# Main.net
KiCad netlist of a schematic drawn in EAGLE
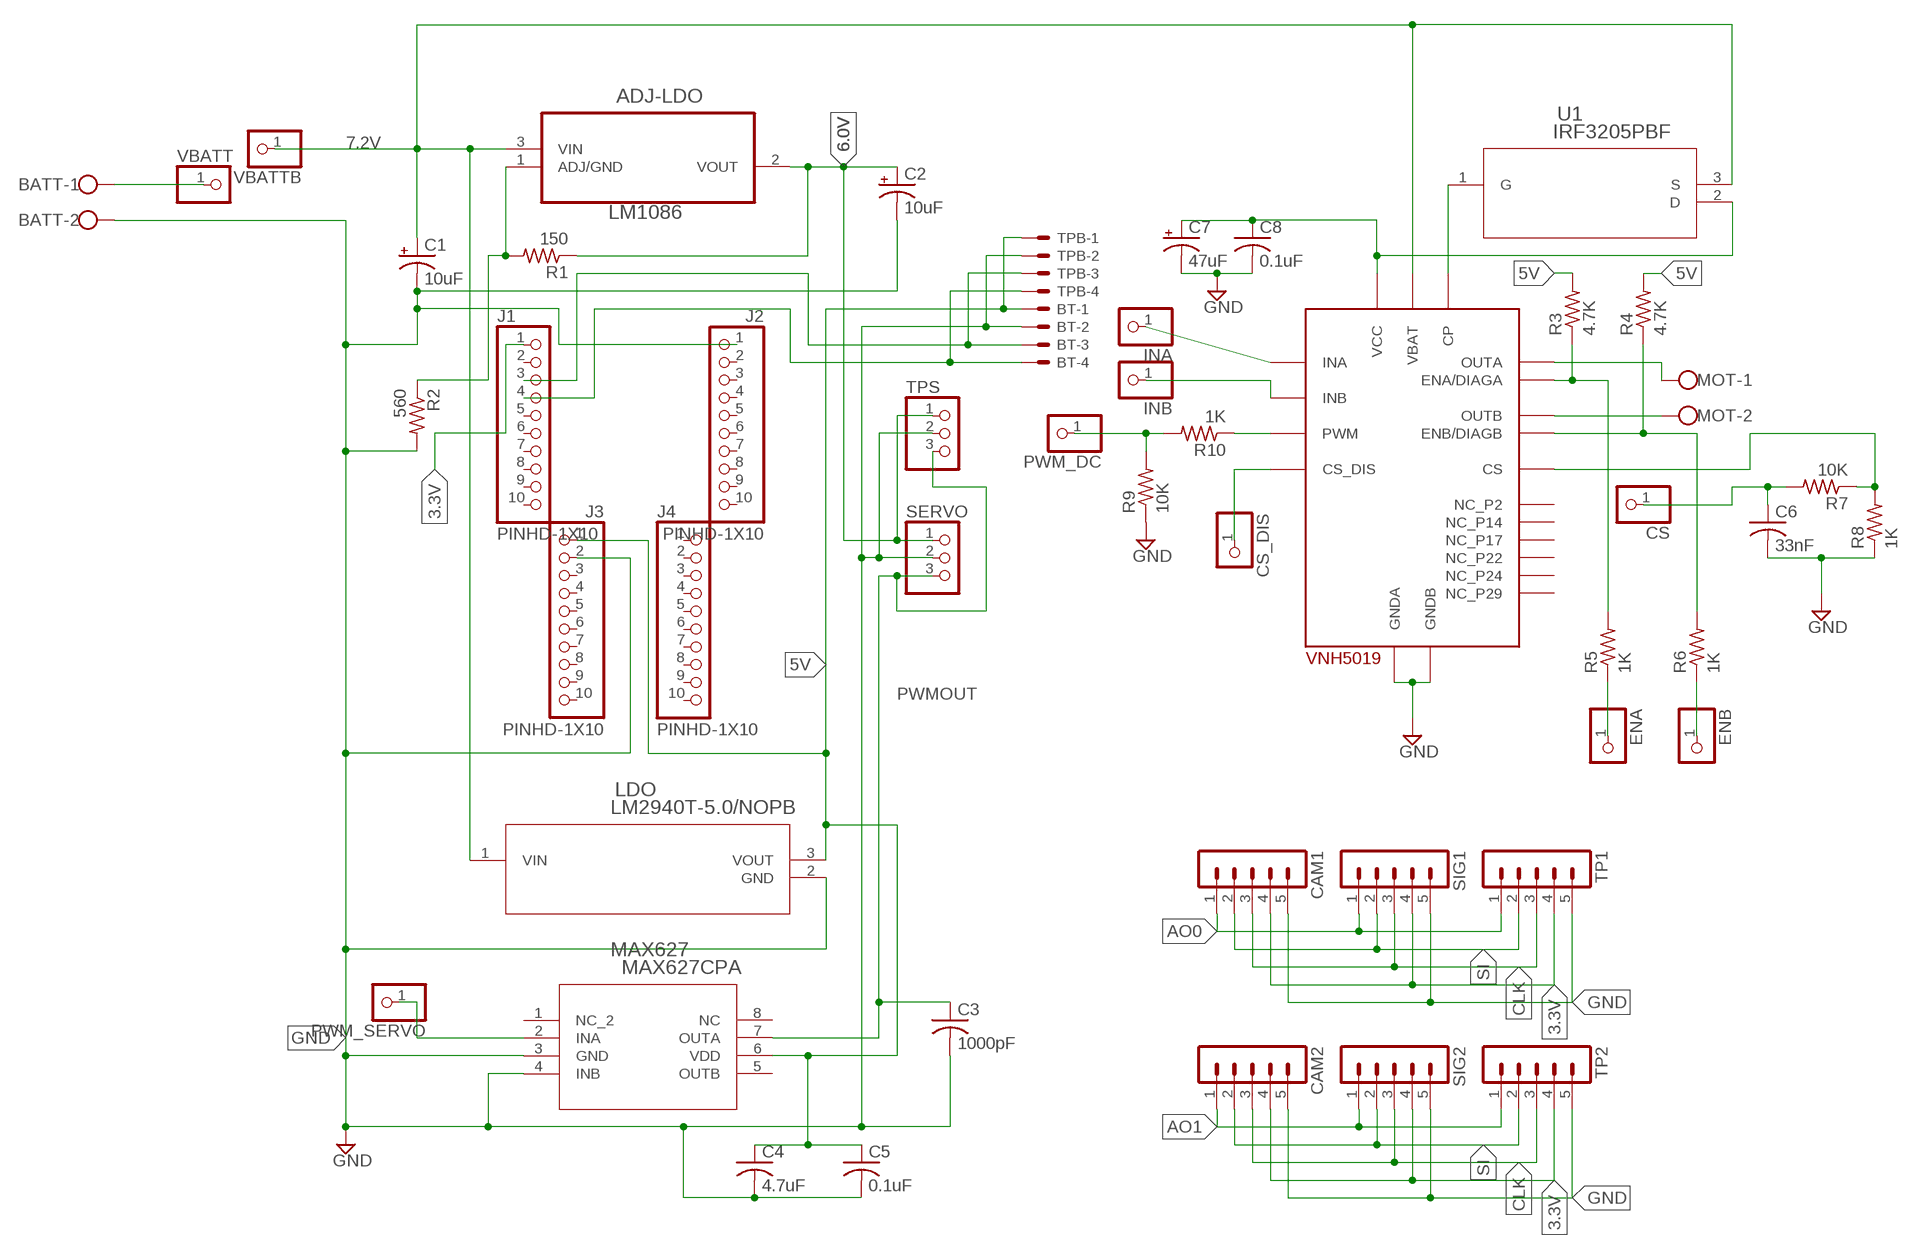
[diagram p0: schematic, sheet 1]

(export (version "E")
  (design (tool "Eeschema 10.0.6"))
  (components
    (comp (ref "ADJ-LDO")
      (value "LM1086")
      (footprint "eagle-import:TO254P470X1016X2222-3P")
      (fields (field (name "MF") "Texas Instruments") (field (name "MP") "LM1086CT-ADJ/NOPB"))
      (libsource (lib "eagle-import") (part "LM1086CT-ADJ/NOPB"))
    )
    (comp (ref "BATT")
      (value "W237-102")
      (footprint "eagle-import:W237-102")
      (fields (field (name "MPN") "237-102"))
      (libsource (lib "eagle-import") (part "W237-102"))
    )
    (comp (ref "BT")
      (value "22-23-2041")
      (footprint "eagle-import:22-23-2041")
      (fields (field (name "MF") "MOLEX"))
      (libsource (lib "eagle-import") (part "22-23-2041"))
    )
    (comp (ref "C1")
      (value "10uF")
      (footprint "eagle-import:E5-10,5")
      (libsource (lib "eagle-import") (part "CPOL-USE5-10.5"))
    )
    (comp (ref "C2")
      (value "10uF")
      (footprint "eagle-import:E5-10,5")
      (libsource (lib "eagle-import") (part "CPOL-USE5-10.5"))
    )
    (comp (ref "C3")
      (value "1000pF")
      (footprint "eagle-import:C050-025X075")
      (libsource (lib "eagle-import") (part "C-US050-025X075"))
    )
    (comp (ref "C4")
      (value "4.7uF")
      (footprint "eagle-import:C050-025X075")
      (libsource (lib "eagle-import") (part "C-US050-025X075"))
    )
    (comp (ref "C5")
      (value "0.1uF")
      (footprint "eagle-import:C050-025X075")
      (libsource (lib "eagle-import") (part "C-US050-025X075"))
    )
    (comp (ref "C6")
      (value "33nF")
      (footprint "eagle-import:C050-025X075")
      (libsource (lib "eagle-import") (part "C-US050-025X075"))
    )
    (comp (ref "C7")
      (value "47uF")
      (footprint "eagle-import:E5-10,5")
      (libsource (lib "eagle-import") (part "CPOL-USE5-10.5"))
    )
    (comp (ref "C8")
      (value "0.1uF")
      (footprint "eagle-import:C050-025X075")
      (libsource (lib "eagle-import") (part "C-US050-025X075"))
    )
    (comp (ref "CAM1")
      (value "MA05-1")
      (footprint "eagle-import:MA05-1")
      (libsource (lib "eagle-import") (part "MA05-1"))
    )
    (comp (ref "CAM2")
      (value "MA05-1")
      (footprint "eagle-import:MA05-1")
      (libsource (lib "eagle-import") (part "MA05-1"))
    )
    (comp (ref "CS")
      (value "PINHD-1X1")
      (footprint "eagle-import:1X01")
      (libsource (lib "eagle-import") (part "PINHD-1X1"))
    )
    (comp (ref "CS_DIS")
      (value "PINHD-1X1")
      (footprint "eagle-import:1X01")
      (libsource (lib "eagle-import") (part "PINHD-1X1"))
    )
    (comp (ref "ENA")
      (value "PINHD-1X1")
      (footprint "eagle-import:1X01")
      (libsource (lib "eagle-import") (part "PINHD-1X1"))
    )
    (comp (ref "ENB")
      (value "PINHD-1X1")
      (footprint "eagle-import:1X01")
      (libsource (lib "eagle-import") (part "PINHD-1X1"))
    )
    (comp (ref "INA")
      (value "PINHD-1X1")
      (footprint "eagle-import:1X01")
      (libsource (lib "eagle-import") (part "PINHD-1X1"))
    )
    (comp (ref "INB")
      (value "PINHD-1X1")
      (footprint "eagle-import:1X01")
      (libsource (lib "eagle-import") (part "PINHD-1X1"))
    )
    (comp (ref "J1")
      (value "PINHD-1X10")
      (footprint "eagle-import:1X10-BIG")
      (libsource (lib "eagle-import") (part "PINHD-1X10"))
    )
    (comp (ref "J2")
      (value "PINHD-1X10")
      (footprint "eagle-import:1X10-BIG")
      (libsource (lib "eagle-import") (part "PINHD-1X10"))
    )
    (comp (ref "J3")
      (value "PINHD-1X10")
      (footprint "eagle-import:1X10-BIG")
      (libsource (lib "eagle-import") (part "PINHD-1X10"))
    )
    (comp (ref "J4")
      (value "PINHD-1X10")
      (footprint "eagle-import:1X10-BIG")
      (libsource (lib "eagle-import") (part "PINHD-1X10"))
    )
    (comp (ref "LDO")
      (value "LM2940T-5.0/NOPB")
      (footprint "eagle-import:T03B")
      (fields (field (name "MANUFACTURER_PART_NUMBER") "LM2940T5.0NOPB"))
      (libsource (lib "eagle-import") (part "LM2940T-5.0/NOPB"))
    )
    (comp (ref "MAX627")
      (value "MAX627CPA")
      (footprint "eagle-import:21-0044B_8")
      (fields (field (name "MANUFACTURER_PART_NUMBER") "max627cpa"))
      (libsource (lib "eagle-import") (part "MAX627CPA"))
    )
    (comp (ref "MOT")
      (value "W237-102")
      (footprint "eagle-import:W237-102")
      (fields (field (name "MPN") "237-102"))
      (libsource (lib "eagle-import") (part "W237-102"))
    )
    (comp (ref "PWM_DC")
      (value "PINHD-1X1")
      (footprint "eagle-import:1X01")
      (libsource (lib "eagle-import") (part "PINHD-1X1"))
    )
    (comp (ref "PWM_SERVO")
      (value "PINHD-1X1")
      (footprint "eagle-import:1X01")
      (libsource (lib "eagle-import") (part "PINHD-1X1"))
    )
    (comp (ref "R1")
      (value "150")
      (footprint "eagle-import:0207_10")
      (libsource (lib "eagle-import") (part "R-US_0207/10"))
    )
    (comp (ref "R2")
      (value "560")
      (footprint "eagle-import:0207_10")
      (libsource (lib "eagle-import") (part "R-US_0207/10"))
    )
    (comp (ref "R3")
      (value "4.7K")
      (footprint "eagle-import:0207_10")
      (libsource (lib "eagle-import") (part "R-US_0207/10"))
    )
    (comp (ref "R4")
      (value "4.7K")
      (footprint "eagle-import:0207_10")
      (libsource (lib "eagle-import") (part "R-US_0207/10"))
    )
    (comp (ref "R5")
      (value "1K")
      (footprint "eagle-import:0207_10")
      (libsource (lib "eagle-import") (part "R-US_0207/10"))
    )
    (comp (ref "R6")
      (value "1K")
      (footprint "eagle-import:0207_10")
      (libsource (lib "eagle-import") (part "R-US_0207/10"))
    )
    (comp (ref "R7")
      (value "10K")
      (footprint "eagle-import:0207_10")
      (libsource (lib "eagle-import") (part "R-US_0207/10"))
    )
    (comp (ref "R8")
      (value "1K")
      (footprint "eagle-import:0207_10")
      (libsource (lib "eagle-import") (part "R-US_0207/10"))
    )
    (comp (ref "R9")
      (value "10K")
      (footprint "eagle-import:0207_10")
      (libsource (lib "eagle-import") (part "R-US_0207/10"))
    )
    (comp (ref "R10")
      (value "1K")
      (footprint "eagle-import:0207_10")
      (libsource (lib "eagle-import") (part "R-US_0207/10"))
    )
    (comp (ref "SERVO")
      (value "PINHD-1X3")
      (footprint "eagle-import:1X03")
      (libsource (lib "eagle-import") (part "PINHD-1X3"))
    )
    (comp (ref "SIG1")
      (value "MA05-1")
      (footprint "eagle-import:MA05-1")
      (libsource (lib "eagle-import") (part "MA05-1"))
    )
    (comp (ref "SIG2")
      (value "MA05-1")
      (footprint "eagle-import:MA05-1")
      (libsource (lib "eagle-import") (part "MA05-1"))
    )
    (comp (ref "TP1")
      (value "MA05-1")
      (footprint "eagle-import:MA05-1")
      (libsource (lib "eagle-import") (part "MA05-1"))
    )
    (comp (ref "TP2")
      (value "MA05-1")
      (footprint "eagle-import:MA05-1")
      (libsource (lib "eagle-import") (part "MA05-1"))
    )
    (comp (ref "TPB")
      (value "22-23-2041")
      (footprint "eagle-import:22-23-2041")
      (fields (field (name "MF") "MOLEX"))
      (libsource (lib "eagle-import") (part "22-23-2041"))
    )
    (comp (ref "TPS")
      (value "PINHD-1X3")
      (footprint "eagle-import:1X03")
      (libsource (lib "eagle-import") (part "PINHD-1X3"))
    )
    (comp (ref "U$1")
      (value "VNH5019")
      (footprint "eagle-import:MULTIPOWERSO-30")
      (libsource (lib "eagle-import") (part "VNH5019"))
    )
    (comp (ref "U1")
      (value "IRF3205PBF")
      (footprint "eagle-import:TO-220AB")
      (libsource (lib "eagle-import") (part "IRF3205PBF"))
    )
    (comp (ref "VBATT")
      (value "PINHD-1X1")
      (footprint "eagle-import:1X01")
      (libsource (lib "eagle-import") (part "PINHD-1X1"))
    )
    (comp (ref "VBATTB")
      (value "PINHD-1X1")
      (footprint "eagle-import:1X01")
      (libsource (lib "eagle-import") (part "PINHD-1X1"))
    )
  )
  (nets
    (net (code "1") (name "/7.2V") (class "Default")
      (node (ref "ADJ-LDO") (pin "3") (pinfunction "VIN_3") (pintype "input"))
      (node (ref "C1") (pin "+") (pinfunction "+_+") (pintype "passive"))
      (node (ref "LDO") (pin "1") (pinfunction "VIN_1") (pintype "input"))
      (node (ref "U$1") (pin "P$12") (pinfunction "VBAT_P$12") (pintype "power_in"))
      (node (ref "U1") (pin "3") (pinfunction "S_3") (pintype "passive"))
      (node (ref "VBATTB") (pin "1") (pinfunction "1_1") (pintype "passive"))
    )
    (net (code "2") (name "/PWMOUT") (class "Default")
      (node (ref "C3") (pin "1") (pinfunction "1_1") (pintype "passive"))
      (node (ref "MAX627") (pin "7") (pinfunction "OUTA_7") (pintype "output"))
      (node (ref "SERVO") (pin "3") (pinfunction "3_3") (pintype "passive"))
      (node (ref "TPS") (pin "3") (pinfunction "3_3") (pintype "passive"))
    )
    (net (code "3") (name "3.3V") (class "Default")
      (node (ref "CAM1") (pin "4") (pinfunction "4_4") (pintype "passive"))
      (node (ref "CAM2") (pin "4") (pinfunction "4_4") (pintype "passive"))
      (node (ref "J1") (pin "1") (pinfunction "1_1") (pintype "passive"))
      (node (ref "SIG1") (pin "4") (pinfunction "4_4") (pintype "passive"))
      (node (ref "SIG2") (pin "4") (pinfunction "4_4") (pintype "passive"))
      (node (ref "TP1") (pin "4") (pinfunction "4_4") (pintype "passive"))
      (node (ref "TP2") (pin "4") (pinfunction "4_4") (pintype "passive"))
    )
    (net (code "4") (name "5V") (class "Default")
      (node (ref "BT") (pin "1") (pinfunction "S_1") (pintype "passive"))
      (node (ref "C4") (pin "1") (pinfunction "1_1") (pintype "passive"))
      (node (ref "C5") (pin "1") (pinfunction "1_1") (pintype "passive"))
      (node (ref "J3") (pin "1") (pinfunction "1_1") (pintype "passive"))
      (node (ref "LDO") (pin "3") (pinfunction "VOUT_3") (pintype "output"))
      (node (ref "MAX627") (pin "6") (pinfunction "VDD_6") (pintype "power_in"))
      (node (ref "R3") (pin "2") (pinfunction "2_2") (pintype "passive"))
      (node (ref "R4") (pin "2") (pinfunction "2_2") (pintype "passive"))
      (node (ref "TPB") (pin "1") (pinfunction "S_1") (pintype "passive"))
    )
    (net (code "5") (name "6.0V") (class "Default")
      (node (ref "ADJ-LDO") (pin "2") (pinfunction "VOUT_2") (pintype "output"))
      (node (ref "C2") (pin "+") (pinfunction "+_+") (pintype "passive"))
      (node (ref "R1") (pin "1") (pinfunction "1_1") (pintype "passive"))
      (node (ref "SERVO") (pin "1") (pinfunction "1_1") (pintype "passive"))
      (node (ref "TPS") (pin "1") (pinfunction "1_1") (pintype "passive"))
    )
    (net (code "6") (name "AO0") (class "Default")
      (node (ref "CAM1") (pin "1") (pinfunction "1_1") (pintype "passive"))
      (node (ref "SIG1") (pin "1") (pinfunction "1_1") (pintype "passive"))
      (node (ref "TP1") (pin "1") (pinfunction "1_1") (pintype "passive"))
    )
    (net (code "7") (name "AO1") (class "Default")
      (node (ref "CAM2") (pin "1") (pinfunction "1_1") (pintype "passive"))
      (node (ref "SIG2") (pin "1") (pinfunction "1_1") (pintype "passive"))
      (node (ref "TP2") (pin "1") (pinfunction "1_1") (pintype "passive"))
    )
    (net (code "8") (name "CLK") (class "Default")
      (node (ref "CAM1") (pin "3") (pinfunction "3_3") (pintype "passive"))
      (node (ref "CAM2") (pin "3") (pinfunction "3_3") (pintype "passive"))
      (node (ref "SIG1") (pin "3") (pinfunction "3_3") (pintype "passive"))
      (node (ref "SIG2") (pin "3") (pinfunction "3_3") (pintype "passive"))
      (node (ref "TP1") (pin "3") (pinfunction "3_3") (pintype "passive"))
      (node (ref "TP2") (pin "3") (pinfunction "3_3") (pintype "passive"))
    )
    (net (code "9") (name "GND") (class "Default")
      (node (ref "BATT") (pin "2") (pinfunction "KL_2") (pintype "passive"))
      (node (ref "BT") (pin "2") (pinfunction "S_2") (pintype "passive"))
      (node (ref "C1") (pin "-") (pinfunction "-_-") (pintype "passive"))
      (node (ref "C2") (pin "-") (pinfunction "-_-") (pintype "passive"))
      (node (ref "C3") (pin "2") (pinfunction "2_2") (pintype "passive"))
      (node (ref "C4") (pin "2") (pinfunction "2_2") (pintype "passive"))
      (node (ref "C5") (pin "2") (pinfunction "2_2") (pintype "passive"))
      (node (ref "C6") (pin "2") (pinfunction "2_2") (pintype "passive"))
      (node (ref "C7") (pin "-") (pinfunction "-_-") (pintype "passive"))
      (node (ref "C8") (pin "2") (pinfunction "2_2") (pintype "passive"))
      (node (ref "CAM1") (pin "5") (pinfunction "5_5") (pintype "passive"))
      (node (ref "CAM2") (pin "5") (pinfunction "5_5") (pintype "passive"))
      (node (ref "J2") (pin "1") (pinfunction "1_1") (pintype "passive"))
      (node (ref "J3") (pin "2") (pinfunction "2_2") (pintype "passive"))
      (node (ref "LDO") (pin "2") (pinfunction "GND_2") (pintype "passive"))
      (node (ref "MAX627") (pin "3") (pinfunction "GND_3") (pintype "power_in"))
      (node (ref "MAX627") (pin "4") (pinfunction "INB_4") (pintype "input"))
      (node (ref "R2") (pin "2") (pinfunction "2_2") (pintype "passive"))
      (node (ref "R8") (pin "1") (pinfunction "1_1") (pintype "passive"))
      (node (ref "R9") (pin "1") (pinfunction "1_1") (pintype "passive"))
      (node (ref "SERVO") (pin "2") (pinfunction "2_2") (pintype "passive"))
      (node (ref "SIG1") (pin "5") (pinfunction "5_5") (pintype "passive"))
      (node (ref "SIG2") (pin "5") (pinfunction "5_5") (pintype "passive"))
      (node (ref "TP1") (pin "5") (pinfunction "5_5") (pintype "passive"))
      (node (ref "TP2") (pin "5") (pinfunction "5_5") (pintype "passive"))
      (node (ref "TPB") (pin "2") (pinfunction "S_2") (pintype "passive"))
      (node (ref "TPS") (pin "2") (pinfunction "2_2") (pintype "passive"))
      (node (ref "U$1") (pin "P$18") (pinfunction "GNDB_P$18") (pintype "power_in"))
      (node (ref "U$1") (pin "P$19") (pinfunction "GNDB_P$19") (pintype "power_in"))
      (node (ref "U$1") (pin "P$20") (pinfunction "GNDB_P$20") (pintype "power_in"))
      (node (ref "U$1") (pin "P$26") (pinfunction "GNDA_P$26") (pintype "power_in"))
      (node (ref "U$1") (pin "P$27") (pinfunction "GNDA_P$27") (pintype "power_in"))
      (node (ref "U$1") (pin "P$28") (pinfunction "GNDA_P$28") (pintype "power_in"))
    )
    (net (code "10") (name "Net-(ADJ-LDO-ADJ{slash}GND)") (class "Default")
      (node (ref "ADJ-LDO") (pin "1") (pinfunction "ADJ/GND_1") (pintype "passive"))
      (node (ref "R1") (pin "2") (pinfunction "2_2") (pintype "passive"))
      (node (ref "R2") (pin "1") (pinfunction "1_1") (pintype "passive"))
    )
    (net (code "11") (name "Net-(BATTA-KL)") (class "Default")
      (node (ref "BATT") (pin "1") (pinfunction "KL_1") (pintype "passive"))
      (node (ref "VBATT") (pin "1") (pinfunction "1_1") (pintype "passive"))
    )
    (net (code "12") (name "Net-(BTC-S)") (class "Default")
      (node (ref "BT") (pin "3") (pinfunction "S_3") (pintype "passive"))
      (node (ref "J1") (pin "3") (pinfunction "3_3") (pintype "passive"))
      (node (ref "TPB") (pin "3") (pinfunction "S_3") (pintype "passive"))
    )
    (net (code "13") (name "Net-(BTD-S)") (class "Default")
      (node (ref "BT") (pin "4") (pinfunction "S_4") (pintype "passive"))
      (node (ref "J1") (pin "4") (pinfunction "4_4") (pintype "passive"))
      (node (ref "TPB") (pin "4") (pinfunction "S_4") (pintype "passive"))
    )
    (net (code "14") (name "Net-(C6-Pad1)") (class "Default")
      (node (ref "C6") (pin "1") (pinfunction "1_1") (pintype "passive"))
      (node (ref "CS") (pin "1") (pinfunction "1_1") (pintype "passive"))
      (node (ref "R7") (pin "2") (pinfunction "2_2") (pintype "passive"))
    )
    (net (code "15") (name "Net-(ENA-Pad1)") (class "Default")
      (node (ref "ENA") (pin "1") (pinfunction "1_1") (pintype "passive"))
      (node (ref "R5") (pin "1") (pinfunction "1_1") (pintype "passive"))
    )
    (net (code "16") (name "Net-(ENB-Pad1)") (class "Default")
      (node (ref "ENB") (pin "1") (pinfunction "1_1") (pintype "passive"))
      (node (ref "R6") (pin "1") (pinfunction "1_1") (pintype "passive"))
    )
    (net (code "17") (name "Net-(MAX627-INA)") (class "Default")
      (node (ref "MAX627") (pin "2") (pinfunction "INA_2") (pintype "input"))
      (node (ref "PWM_SERVO") (pin "1") (pinfunction "1_1") (pintype "passive"))
    )
    (net (code "18") (name "Net-(MOTA-KL)") (class "Default")
      (node (ref "MOT") (pin "1") (pinfunction "KL_1") (pintype "passive"))
      (node (ref "U$1") (pin "P$1") (pinfunction "OUTA_P$1") (pintype "output"))
      (node (ref "U$1") (pin "P$25") (pinfunction "OUTA_P$25") (pintype "output"))
      (node (ref "U$1") (pin "P$30") (pinfunction "OUTA_P$30") (pintype "output"))
      (node (ref "U$1") (pin "P$32") (pinfunction "OUTA_P$32") (pintype "output"))
    )
    (net (code "19") (name "Net-(MOTB-KL)") (class "Default")
      (node (ref "MOT") (pin "2") (pinfunction "KL_2") (pintype "passive"))
      (node (ref "U$1") (pin "P$15") (pinfunction "OUTB_P$15") (pintype "output"))
      (node (ref "U$1") (pin "P$16") (pinfunction "OUTB_P$16") (pintype "output"))
      (node (ref "U$1") (pin "P$21") (pinfunction "OUTB_P$21") (pintype "output"))
      (node (ref "U$1") (pin "P$33") (pinfunction "OUTB_P$33") (pintype "output"))
    )
    (net (code "20") (name "Net-(PWM_DC-Pad1)") (class "Default")
      (node (ref "PWM_DC") (pin "1") (pinfunction "1_1") (pintype "passive"))
      (node (ref "R10") (pin "2") (pinfunction "2_2") (pintype "passive"))
      (node (ref "R9") (pin "2") (pinfunction "2_2") (pintype "passive"))
    )
    (net (code "21") (name "Net-(U$1-CP)") (class "Default")
      (node (ref "U$1") (pin "P$11") (pinfunction "CP_P$11") (pintype "bidirectional"))
      (node (ref "U1") (pin "1") (pinfunction "G_1") (pintype "passive"))
    )
    (net (code "22") (name "Net-(U$1-CS)") (class "Default")
      (node (ref "R7") (pin "1") (pinfunction "1_1") (pintype "passive"))
      (node (ref "R8") (pin "2") (pinfunction "2_2") (pintype "passive"))
      (node (ref "U$1") (pin "P$8") (pinfunction "CS_P$8") (pintype "output"))
    )
    (net (code "23") (name "Net-(U$1-CS_DIS)") (class "Default")
      (node (ref "CS_DIS") (pin "1") (pinfunction "1_1") (pintype "passive"))
      (node (ref "U$1") (pin "P$6") (pinfunction "CS_DIS_P$6") (pintype "input"))
    )
    (net (code "24") (name "Net-(U$1-ENA{slash}DIAGA)") (class "Default")
      (node (ref "R3") (pin "1") (pinfunction "1_1") (pintype "passive"))
      (node (ref "R5") (pin "2") (pinfunction "2_2") (pintype "passive"))
      (node (ref "U$1") (pin "P$5") (pinfunction "ENA/DIAGA_P$5") (pintype "output"))
    )
    (net (code "25") (name "Net-(U$1-ENB{slash}DIAGB)") (class "Default")
      (node (ref "R4") (pin "1") (pinfunction "1_1") (pintype "passive"))
      (node (ref "R6") (pin "2") (pinfunction "2_2") (pintype "passive"))
      (node (ref "U$1") (pin "P$9") (pinfunction "ENB/DIAGB_P$9") (pintype "output"))
    )
    (net (code "26") (name "Net-(U$1-INA)") (class "Default")
      (node (ref "INA") (pin "1") (pinfunction "1_1") (pintype "passive"))
      (node (ref "U$1") (pin "P$4") (pinfunction "INA_P$4") (pintype "input"))
    )
    (net (code "27") (name "Net-(U$1-INB)") (class "Default")
      (node (ref "INB") (pin "1") (pinfunction "1_1") (pintype "passive"))
      (node (ref "U$1") (pin "P$10") (pinfunction "INB_P$10") (pintype "input"))
    )
    (net (code "28") (name "Net-(U$1-PWM)") (class "Default")
      (node (ref "R10") (pin "1") (pinfunction "1_1") (pintype "passive"))
      (node (ref "U$1") (pin "P$7") (pinfunction "PWM_P$7") (pintype "input"))
    )
    (net (code "29") (name "Net-(U1-D)") (class "Default")
      (node (ref "C7") (pin "+") (pinfunction "+_+") (pintype "passive"))
      (node (ref "C8") (pin "1") (pinfunction "1_1") (pintype "passive"))
      (node (ref "U$1") (pin "P$13") (pinfunction "VCC_P$13") (pintype "power_in"))
      (node (ref "U$1") (pin "P$23") (pinfunction "VCC_P$23") (pintype "power_in"))
      (node (ref "U$1") (pin "P$3") (pinfunction "VCC_P$3") (pintype "power_in"))
      (node (ref "U$1") (pin "P$31") (pinfunction "VCC_P$31") (pintype "power_in"))
      (node (ref "U1") (pin "2") (pinfunction "D_2") (pintype "passive"))
    )
    (net (code "30") (name "SI") (class "Default")
      (node (ref "CAM1") (pin "2") (pinfunction "2_2") (pintype "passive"))
      (node (ref "CAM2") (pin "2") (pinfunction "2_2") (pintype "passive"))
      (node (ref "SIG1") (pin "2") (pinfunction "2_2") (pintype "passive"))
      (node (ref "SIG2") (pin "2") (pinfunction "2_2") (pintype "passive"))
      (node (ref "TP1") (pin "2") (pinfunction "2_2") (pintype "passive"))
      (node (ref "TP2") (pin "2") (pinfunction "2_2") (pintype "passive"))
    )
    (net (code "31") (name "unconnected-(J1-Pad2)") (class "Default")
      (node (ref "J1") (pin "2") (pinfunction "2_2") (pintype "passive"))
    )
    (net (code "32") (name "unconnected-(J1-Pad5)") (class "Default")
      (node (ref "J1") (pin "5") (pinfunction "5_5") (pintype "passive"))
    )
    (net (code "33") (name "unconnected-(J1-Pad6)") (class "Default")
      (node (ref "J1") (pin "6") (pinfunction "6_6") (pintype "passive"))
    )
    (net (code "34") (name "unconnected-(J1-Pad7)") (class "Default")
      (node (ref "J1") (pin "7") (pinfunction "7_7") (pintype "passive"))
    )
    (net (code "35") (name "unconnected-(J1-Pad8)") (class "Default")
      (node (ref "J1") (pin "8") (pinfunction "8_8") (pintype "passive"))
    )
    (net (code "36") (name "unconnected-(J1-Pad9)") (class "Default")
      (node (ref "J1") (pin "9") (pinfunction "9_9") (pintype "passive"))
    )
    (net (code "37") (name "unconnected-(J1-Pad10)") (class "Default")
      (node (ref "J1") (pin "10") (pinfunction "10_10") (pintype "passive"))
    )
    (net (code "38") (name "unconnected-(J2-Pad2)") (class "Default")
      (node (ref "J2") (pin "2") (pinfunction "2_2") (pintype "passive"))
    )
    (net (code "39") (name "unconnected-(J2-Pad3)") (class "Default")
      (node (ref "J2") (pin "3") (pinfunction "3_3") (pintype "passive"))
    )
    (net (code "40") (name "unconnected-(J2-Pad4)") (class "Default")
      (node (ref "J2") (pin "4") (pinfunction "4_4") (pintype "passive"))
    )
    (net (code "41") (name "unconnected-(J2-Pad5)") (class "Default")
      (node (ref "J2") (pin "5") (pinfunction "5_5") (pintype "passive"))
    )
    (net (code "42") (name "unconnected-(J2-Pad6)") (class "Default")
      (node (ref "J2") (pin "6") (pinfunction "6_6") (pintype "passive"))
    )
    (net (code "43") (name "unconnected-(J2-Pad7)") (class "Default")
      (node (ref "J2") (pin "7") (pinfunction "7_7") (pintype "passive"))
    )
    (net (code "44") (name "unconnected-(J2-Pad8)") (class "Default")
      (node (ref "J2") (pin "8") (pinfunction "8_8") (pintype "passive"))
    )
    (net (code "45") (name "unconnected-(J2-Pad9)") (class "Default")
      (node (ref "J2") (pin "9") (pinfunction "9_9") (pintype "passive"))
    )
    (net (code "46") (name "unconnected-(J2-Pad10)") (class "Default")
      (node (ref "J2") (pin "10") (pinfunction "10_10") (pintype "passive"))
    )
    (net (code "47") (name "unconnected-(J3-Pad3)") (class "Default")
      (node (ref "J3") (pin "3") (pinfunction "3_3") (pintype "passive"))
    )
    (net (code "48") (name "unconnected-(J3-Pad4)") (class "Default")
      (node (ref "J3") (pin "4") (pinfunction "4_4") (pintype "passive"))
    )
    (net (code "49") (name "unconnected-(J3-Pad5)") (class "Default")
      (node (ref "J3") (pin "5") (pinfunction "5_5") (pintype "passive"))
    )
    (net (code "50") (name "unconnected-(J3-Pad6)") (class "Default")
      (node (ref "J3") (pin "6") (pinfunction "6_6") (pintype "passive"))
    )
    (net (code "51") (name "unconnected-(J3-Pad7)") (class "Default")
      (node (ref "J3") (pin "7") (pinfunction "7_7") (pintype "passive"))
    )
    (net (code "52") (name "unconnected-(J3-Pad8)") (class "Default")
      (node (ref "J3") (pin "8") (pinfunction "8_8") (pintype "passive"))
    )
    (net (code "53") (name "unconnected-(J3-Pad9)") (class "Default")
      (node (ref "J3") (pin "9") (pinfunction "9_9") (pintype "passive"))
    )
    (net (code "54") (name "unconnected-(J3-Pad10)") (class "Default")
      (node (ref "J3") (pin "10") (pinfunction "10_10") (pintype "passive"))
    )
    (net (code "55") (name "unconnected-(J4-Pad1)") (class "Default")
      (node (ref "J4") (pin "1") (pinfunction "1_1") (pintype "passive"))
    )
    (net (code "56") (name "unconnected-(J4-Pad2)") (class "Default")
      (node (ref "J4") (pin "2") (pinfunction "2_2") (pintype "passive"))
    )
    (net (code "57") (name "unconnected-(J4-Pad3)") (class "Default")
      (node (ref "J4") (pin "3") (pinfunction "3_3") (pintype "passive"))
    )
    (net (code "58") (name "unconnected-(J4-Pad4)") (class "Default")
      (node (ref "J4") (pin "4") (pinfunction "4_4") (pintype "passive"))
    )
    (net (code "59") (name "unconnected-(J4-Pad5)") (class "Default")
      (node (ref "J4") (pin "5") (pinfunction "5_5") (pintype "passive"))
    )
    (net (code "60") (name "unconnected-(J4-Pad6)") (class "Default")
      (node (ref "J4") (pin "6") (pinfunction "6_6") (pintype "passive"))
    )
    (net (code "61") (name "unconnected-(J4-Pad7)") (class "Default")
      (node (ref "J4") (pin "7") (pinfunction "7_7") (pintype "passive"))
    )
    (net (code "62") (name "unconnected-(J4-Pad8)") (class "Default")
      (node (ref "J4") (pin "8") (pinfunction "8_8") (pintype "passive"))
    )
    (net (code "63") (name "unconnected-(J4-Pad9)") (class "Default")
      (node (ref "J4") (pin "9") (pinfunction "9_9") (pintype "passive"))
    )
    (net (code "64") (name "unconnected-(J4-Pad10)") (class "Default")
      (node (ref "J4") (pin "10") (pinfunction "10_10") (pintype "passive"))
    )
    (net (code "65") (name "unconnected-(MAX627-NC-Pad8)") (class "Default")
      (node (ref "MAX627") (pin "8") (pinfunction "NC_8") (pintype "no_connect"))
    )
    (net (code "66") (name "unconnected-(MAX627-NC_2-Pad1)") (class "Default")
      (node (ref "MAX627") (pin "1") (pinfunction "NC_2_1") (pintype "no_connect"))
    )
    (net (code "67") (name "unconnected-(MAX627-OUTB-Pad5)") (class "Default")
      (node (ref "MAX627") (pin "5") (pinfunction "OUTB_5") (pintype "output"))
    )
    (net (code "68") (name "unconnected-(U$1-NC_P2-PadP$2)") (class "Default")
      (node (ref "U$1") (pin "P$2") (pinfunction "NC_P2_P$2") (pintype "bidirectional"))
    )
    (net (code "69") (name "unconnected-(U$1-NC_P14-PadP$14)") (class "Default")
      (node (ref "U$1") (pin "P$14") (pinfunction "NC_P14_P$14") (pintype "bidirectional"))
    )
    (net (code "70") (name "unconnected-(U$1-NC_P17-PadP$17)") (class "Default")
      (node (ref "U$1") (pin "P$17") (pinfunction "NC_P17_P$17") (pintype "bidirectional"))
    )
    (net (code "71") (name "unconnected-(U$1-NC_P22-PadP$22)") (class "Default")
      (node (ref "U$1") (pin "P$22") (pinfunction "NC_P22_P$22") (pintype "bidirectional"))
    )
    (net (code "72") (name "unconnected-(U$1-NC_P24-PadP$24)") (class "Default")
      (node (ref "U$1") (pin "P$24") (pinfunction "NC_P24_P$24") (pintype "bidirectional"))
    )
    (net (code "73") (name "unconnected-(U$1-NC_P29-PadP$29)") (class "Default")
      (node (ref "U$1") (pin "P$29") (pinfunction "NC_P29_P$29") (pintype "bidirectional"))
    )
  )
)
